# 5VSupply.net
KiCad netlist of a schematic drawn in Altium Designer
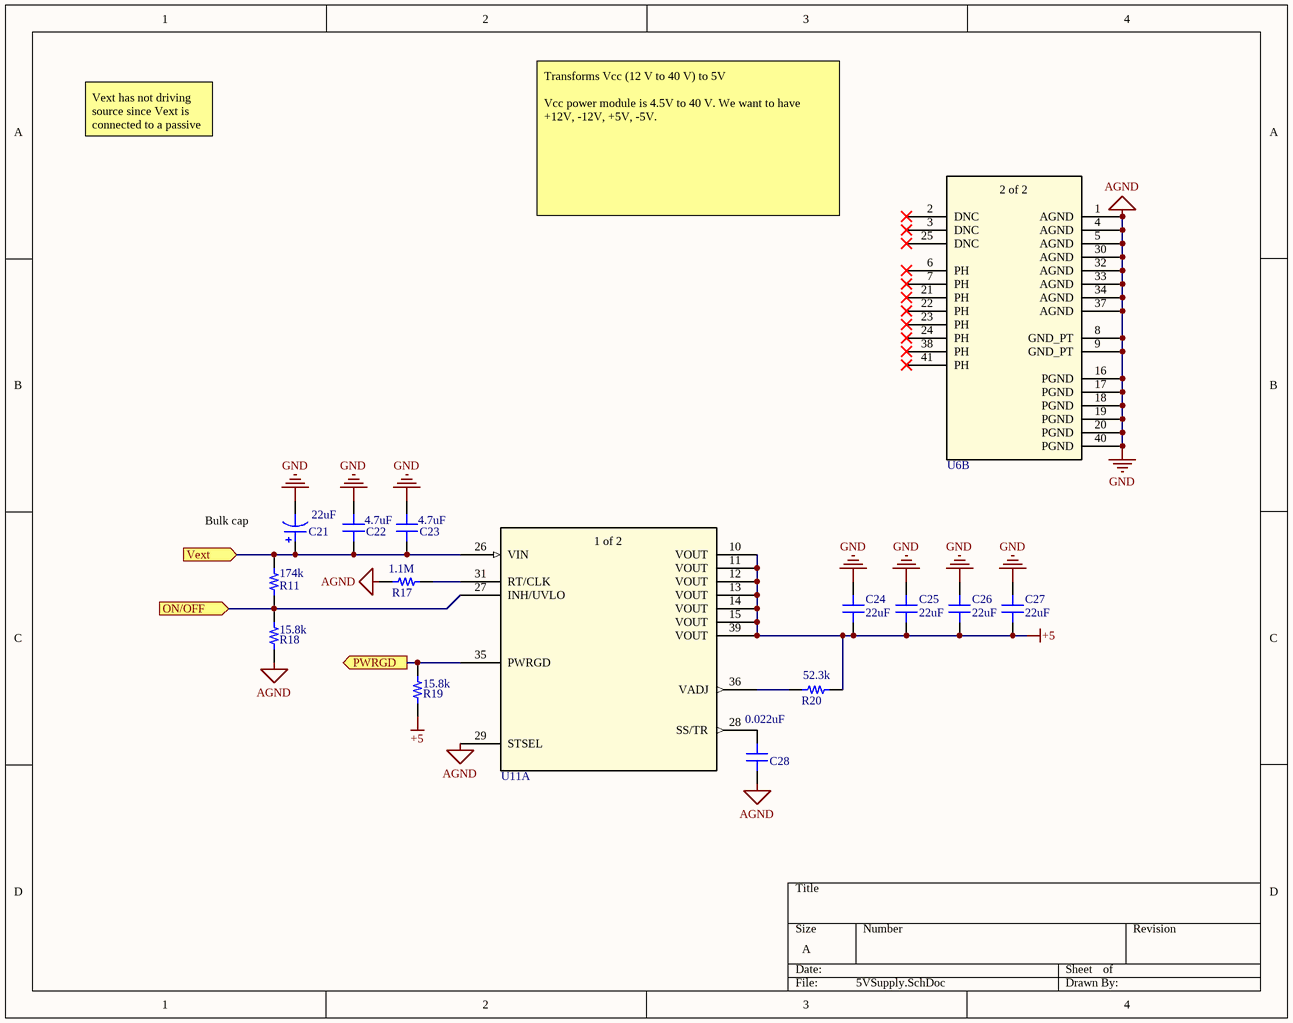
[diagram p0: 5VSupply.SchDoc]

(export (version "E")
  (design (tool "Eeschema 10.0.6"))
  (components
    (comp (ref "C21")
      (value "22uF")
      (footprint "CAP AL TH D8 L3.5 H11.5")
      (description "CAP ALUM 22UF 20% 100V RADIAL")
      (fields
        (field (name "PART NUMBER") "EEU-FC2A220")
        (field (name "MANUFACTURER") "Panasonic Electronic Components")
      )
      (libsource (lib "Celestial Library Database") (part "Polarised Capacitor"))
    )
    (comp (ref "C22")
      (value "4.7uF")
      (footprint "CAP 1206/3216 - 1.0MM")
      (description "CAP CER 4.7UF 50V X5R 1206")
      (fields
        (field (name "PART NUMBER") "C3216X5R1H475K085AB")
        (field (name "MANUFACTURER") "TDK Corporation")
      )
      (libsource (lib "Celestial Library Database") (part "Capacitor"))
    )
    (comp (ref "C23")
      (value "4.7uF")
      (footprint "CAP 1206/3216 - 1.0MM")
      (description "CAP CER 4.7UF 50V X5R 1206")
      (fields
        (field (name "PART NUMBER") "C3216X5R1H475K085AB")
        (field (name "MANUFACTURER") "TDK Corporation")
      )
      (libsource (lib "Celestial Library Database") (part "Capacitor"))
    )
    (comp (ref "C24")
      (value "22uF")
      (footprint "CAP 1206/3216")
      (description "CAP CER 22UF 25V X5R 1206")
      (fields
        (field (name "PART NUMBER") "CL31A226KAHNNNE")
        (field (name "MANUFACTURER") "Samsung Electro-Mechanics America, Inc.")
      )
      (libsource (lib "Celestial Library Database") (part "Capacitor"))
    )
    (comp (ref "C25")
      (value "22uF")
      (footprint "CAP 1206/3216")
      (description "CAP CER 22UF 25V X5R 1206")
      (fields
        (field (name "PART NUMBER") "CL31A226KAHNNNE")
        (field (name "MANUFACTURER") "Samsung Electro-Mechanics America, Inc.")
      )
      (libsource (lib "Celestial Library Database") (part "Capacitor"))
    )
    (comp (ref "C26")
      (value "22uF")
      (footprint "CAP 1206/3216")
      (description "CAP CER 22UF 25V X5R 1206")
      (fields
        (field (name "PART NUMBER") "CL31A226KAHNNNE")
        (field (name "MANUFACTURER") "Samsung Electro-Mechanics America, Inc.")
      )
      (libsource (lib "Celestial Library Database") (part "Capacitor"))
    )
    (comp (ref "C27")
      (value "22uF")
      (footprint "CAP 1206/3216")
      (description "CAP CER 22UF 25V X5R 1206")
      (fields
        (field (name "PART NUMBER") "CL31A226KAHNNNE")
        (field (name "MANUFACTURER") "Samsung Electro-Mechanics America, Inc.")
      )
      (libsource (lib "Celestial Library Database") (part "Capacitor"))
    )
    (comp (ref "C28")
      (value "0.022uF")
      (footprint "CAP 0805/2012")
      (description "CAP CER 0.022UF 100V X7R 0805")
      (fields (field (name "PART NUMBER") "C0805S223K1RAC7800") (field (name "MANUFACTURER") "Kemet"))
      (libsource (lib "Celestial Library Database") (part "Capacitor"))
    )
    (comp (ref "R11")
      (value "174k")
      (footprint "RES 0805/2012")
      (description "RES SMD 174K OHM 1% 1/8W 0805")
      (fields
        (field (name "PART NUMBER") "ERJ-6ENF1743V")
        (field (name "MANUFACTURER") "Panasonic Electronic Components")
      )
      (libsource (lib "Celestial Library Database") (part "Resistor"))
    )
    (comp (ref "R17")
      (value "1.1M")
      (footprint "RES 0603/1608")
      (description "RES SMD 1.1M OHM 1% 1/10W 0603")
      (fields
        (field (name "PART NUMBER") "ERJ-3EKF1104V")
        (field (name "MANUFACTURER") "Panasonic Electronic Components")
      )
      (libsource (lib "Celestial Library Database") (part "Resistor"))
    )
    (comp (ref "R18")
      (value "15.8k")
      (footprint "RES 0805/2012")
      (description "RES SMD 15.8K OHM 1% 1/8W 0805")
      (fields
        (field (name "PART NUMBER") "ERJ-6ENF1582V")
        (field (name "MANUFACTURER") "Panasonic Electronic Components")
      )
      (libsource (lib "Celestial Library Database") (part "Resistor"))
    )
    (comp (ref "R19")
      (value "15.8k")
      (footprint "RES 0805/2012")
      (description "RES SMD 15.8K OHM 1% 1/8W 0805")
      (fields
        (field (name "PART NUMBER") "ERJ-6ENF1582V")
        (field (name "MANUFACTURER") "Panasonic Electronic Components")
      )
      (libsource (lib "Celestial Library Database") (part "Resistor"))
    )
    (comp (ref "R20")
      (value "52.3k")
      (footprint "RES 0603/1608")
      (description "RES SMD 52.3KOHM 0.1% 1/10W 0603")
      (fields
        (field (name "PART NUMBER") "ERA-3AEB5232V")
        (field (name "MANUFACTURER") "Panasonic Electronic Components")
      )
      (libsource (lib "Celestial Library Database") (part "Resistor"))
    )
    (comp (ref "U6")
      (value "LMZ34003")
      (footprint "RKG41")
      (description "DC DC CONVERTER 2.5-15V 38W")
      (fields
        (field (name "MANUFACTURER_PART_NUMBER") "LMZ34002RKGT")
        (field (name "MANUFACTURER") "Texas Instruments")
        (field (name "COPYRIGHT") "Copyright (C) 2018 Accelerated Designs. All rights reserved")
      )
      (libsource (lib "Celestial Library Database") (part "LMZ34003RKGT"))
    )
    (comp (ref "U11")
      (value "LMZ35003RKGR")
      (footprint "RKG41")
      (description "DC DC CONVERTER 2.5-15V 38W")
      (fields
        (field (name "MANUFACTURER_PART_NUMBER") "LMZ34002RKGT")
        (field (name "PART NUMBER") "LMZ34003")
        (field (name "COPYRIGHT") "Copyright (C) 2018 Accelerated Designs. All rights reserved")
      )
      (libsource (lib "Celestial Library Database") (part "LMZ34003RKGT"))
    )
  )
  (nets
    (net (code "1") (name "+5") (class "Default")
      (node (ref "C24") (pin "2") (pinfunction "2_2") (pintype "passive"))
      (node (ref "C25") (pin "2") (pinfunction "2_2") (pintype "passive"))
      (node (ref "C26") (pin "2") (pinfunction "2_2") (pintype "passive"))
      (node (ref "C27") (pin "2") (pinfunction "2_2") (pintype "passive"))
      (node (ref "R19") (pin "1") (pinfunction "1_1") (pintype "passive"))
      (node (ref "R20") (pin "2") (pinfunction "2_2") (pintype "passive"))
      (node (ref "U11") (pin "10") (pinfunction "VOUT_10") (pintype "power_in"))
      (node (ref "U11") (pin "11") (pinfunction "VOUT_11") (pintype "power_in"))
      (node (ref "U11") (pin "12") (pinfunction "VOUT_12") (pintype "power_in"))
      (node (ref "U11") (pin "13") (pinfunction "VOUT_13") (pintype "power_in"))
      (node (ref "U11") (pin "14") (pinfunction "VOUT_14") (pintype "power_in"))
      (node (ref "U11") (pin "15") (pinfunction "VOUT_15") (pintype "power_in"))
      (node (ref "U11") (pin "39") (pinfunction "VOUT_39") (pintype "power_in"))
    )
    (net (code "2") (name "/ON{slash}OFF") (class "Default")
      (node (ref "R11") (pin "1") (pinfunction "1_1") (pintype "passive"))
      (node (ref "R18") (pin "2") (pinfunction "2_2") (pintype "passive"))
      (node (ref "U11") (pin "27") (pinfunction "INH/UVLO_27") (pintype "passive"))
    )
    (net (code "3") (name "/PWRGD") (class "Default")
      (node (ref "R19") (pin "2") (pinfunction "2_2") (pintype "passive"))
      (node (ref "U11") (pin "35") (pinfunction "PWRGD_35") (pintype "open_emitter"))
    )
    (net (code "4") (name "/Vext") (class "Default")
      (node (ref "C21") (pin "1") (pinfunction "1_1") (pintype "passive"))
      (node (ref "C22") (pin "1") (pinfunction "1_1") (pintype "passive"))
      (node (ref "C23") (pin "1") (pinfunction "1_1") (pintype "passive"))
      (node (ref "R11") (pin "2") (pinfunction "2_2") (pintype "passive"))
      (node (ref "U11") (pin "26") (pinfunction "VIN_26") (pintype "input"))
    )
    (net (code "5") (name "AGND") (class "Default")
      (node (ref "C21") (pin "2") (pinfunction "2_2") (pintype "passive"))
      (node (ref "C22") (pin "2") (pinfunction "2_2") (pintype "passive"))
      (node (ref "C23") (pin "2") (pinfunction "2_2") (pintype "passive"))
      (node (ref "C24") (pin "1") (pinfunction "1_1") (pintype "passive"))
      (node (ref "C25") (pin "1") (pinfunction "1_1") (pintype "passive"))
      (node (ref "C26") (pin "1") (pinfunction "1_1") (pintype "passive"))
      (node (ref "C27") (pin "1") (pinfunction "1_1") (pintype "passive"))
      (node (ref "C28") (pin "1") (pinfunction "1_1") (pintype "passive"))
      (node (ref "R17") (pin "1") (pinfunction "1_1") (pintype "passive"))
      (node (ref "R18") (pin "1") (pinfunction "1_1") (pintype "passive"))
      (node (ref "U11") (pin "29") (pinfunction "STSEL_29") (pintype "passive"))
      (node (ref "U6") (pin "1") (pinfunction "AGND_1") (pintype "power_in"))
      (node (ref "U6") (pin "16") (pinfunction "PGND_16") (pintype "power_in"))
      (node (ref "U6") (pin "17") (pinfunction "PGND_17") (pintype "power_in"))
      (node (ref "U6") (pin "18") (pinfunction "PGND_18") (pintype "power_in"))
      (node (ref "U6") (pin "19") (pinfunction "PGND_19") (pintype "power_in"))
      (node (ref "U6") (pin "20") (pinfunction "PGND_20") (pintype "power_in"))
      (node (ref "U6") (pin "30") (pinfunction "AGND_30") (pintype "power_in"))
      (node (ref "U6") (pin "32") (pinfunction "AGND_32") (pintype "power_in"))
      (node (ref "U6") (pin "33") (pinfunction "AGND_33") (pintype "power_in"))
      (node (ref "U6") (pin "34") (pinfunction "AGND_34") (pintype "power_in"))
      (node (ref "U6") (pin "37") (pinfunction "AGND_37") (pintype "power_in"))
      (node (ref "U6") (pin "4") (pinfunction "AGND_4") (pintype "power_in"))
      (node (ref "U6") (pin "40") (pinfunction "PGND_40") (pintype "power_in"))
      (node (ref "U6") (pin "5") (pinfunction "AGND_5") (pintype "power_in"))
      (node (ref "U6") (pin "8") (pinfunction "GND_PT_8") (pintype "power_in"))
      (node (ref "U6") (pin "9") (pinfunction "GND_PT_9") (pintype "power_in"))
    )
    (net (code "6") (name "Net-(U11A-RT{slash}CLK)") (class "Default")
      (node (ref "R17") (pin "2") (pinfunction "2_2") (pintype "passive"))
      (node (ref "U11") (pin "31") (pinfunction "RT/CLK_31") (pintype "passive"))
    )
    (net (code "7") (name "Net-(U11A-SS{slash}TR)") (class "Default")
      (node (ref "C28") (pin "2") (pinfunction "2_2") (pintype "passive"))
      (node (ref "U11") (pin "28") (pinfunction "SS/TR_28") (pintype "output"))
    )
    (net (code "8") (name "Net-(U11A-VADJ)") (class "Default")
      (node (ref "R20") (pin "1") (pinfunction "1_1") (pintype "passive"))
      (node (ref "U11") (pin "36") (pinfunction "VADJ_36") (pintype "output"))
    )
    (net (code "9") (name "unconnected-(U6B-DNC-Pad2)") (class "Default")
      (node (ref "U6") (pin "2") (pinfunction "DNC_2") (pintype "passive+no_connect"))
    )
    (net (code "10") (name "unconnected-(U6B-DNC-Pad3)") (class "Default")
      (node (ref "U6") (pin "3") (pinfunction "DNC_3") (pintype "passive+no_connect"))
    )
    (net (code "11") (name "unconnected-(U6B-DNC-Pad25)") (class "Default")
      (node (ref "U6") (pin "25") (pinfunction "DNC_25") (pintype "passive+no_connect"))
    )
    (net (code "12") (name "unconnected-(U6B-PH-Pad6)") (class "Default")
      (node (ref "U6") (pin "6") (pinfunction "PH_6") (pintype "passive+no_connect"))
    )
    (net (code "13") (name "unconnected-(U6B-PH-Pad7)") (class "Default")
      (node (ref "U6") (pin "7") (pinfunction "PH_7") (pintype "passive+no_connect"))
    )
    (net (code "14") (name "unconnected-(U6B-PH-Pad21)") (class "Default")
      (node (ref "U6") (pin "21") (pinfunction "PH_21") (pintype "passive+no_connect"))
    )
    (net (code "15") (name "unconnected-(U6B-PH-Pad22)") (class "Default")
      (node (ref "U6") (pin "22") (pinfunction "PH_22") (pintype "passive+no_connect"))
    )
    (net (code "16") (name "unconnected-(U6B-PH-Pad23)") (class "Default")
      (node (ref "U6") (pin "23") (pinfunction "PH_23") (pintype "passive+no_connect"))
    )
    (net (code "17") (name "unconnected-(U6B-PH-Pad24)") (class "Default")
      (node (ref "U6") (pin "24") (pinfunction "PH_24") (pintype "passive+no_connect"))
    )
    (net (code "18") (name "unconnected-(U6B-PH-Pad38)") (class "Default")
      (node (ref "U6") (pin "38") (pinfunction "PH_38") (pintype "passive+no_connect"))
    )
    (net (code "19") (name "unconnected-(U6B-PH-Pad41)") (class "Default")
      (node (ref "U6") (pin "41") (pinfunction "PH_41") (pintype "passive+no_connect"))
    )
  )
)
